# ir-tara-smd.net
KiCad netlist of a schematic drawn in Altium Designer
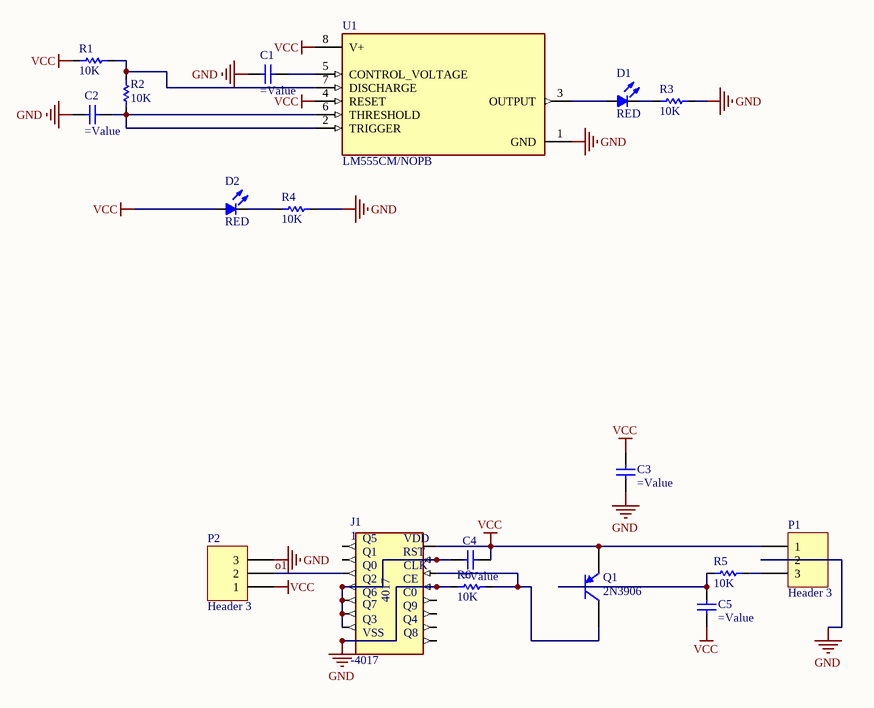
[diagram p0: ir-tara-smd.SchDoc]

(export (version "E")
  (design (tool "Eeschema 10.0.6"))
  (components
    (comp (ref "C1")
      (value "~")
      (footprint "CAP 1206")
      (description "Capacitor")
      (libsource (lib "AltiumLib1") (part "Capacitor"))
    )
    (comp (ref "C2")
      (value "~")
      (footprint "CAP 1206")
      (description "Capacitor")
      (libsource (lib "AltiumLib1") (part "Capacitor"))
    )
    (comp (ref "C3")
      (value "~")
      (footprint "CAP 1206")
      (description "Capacitor")
      (libsource (lib "AltiumLib1") (part "Capacitor"))
    )
    (comp (ref "C4")
      (value "~")
      (footprint "CAP 1206")
      (description "Capacitor")
      (libsource (lib "AltiumLib1") (part "Capacitor"))
    )
    (comp (ref "C5")
      (value "~")
      (footprint "CAP 1206")
      (description "Capacitor")
      (libsource (lib "AltiumLib1") (part "Capacitor"))
    )
    (comp (ref "D1")
      (value "MODEL")
      (footprint "LED-5mm")
      (description "Typical LED")
      (fields (field (name "COLOR") "RED"))
      (libsource (lib "AltiumLib1") (part "LED 5mm"))
    )
    (comp (ref "D2")
      (value "MODEL")
      (footprint "LED-5mm")
      (description "Typical LED")
      (fields (field (name "COLOR") "RED"))
      (libsource (lib "AltiumLib1") (part "LED 5mm"))
    )
    (comp (ref "J1")
      (value "-4017")
      (footprint "SOIC127P600X175-16N")
      (description "10000pF Â±1% 25V Ceramic Capacitor C0G, NP0 0603 (1608 Metric)")
      (fields (field (name "MF") "Heyco") (field (name "MP") "4017"))
      (libsource (lib "-4017") (part "-4017"))
    )
    (comp (ref "P1")
      (value "Header 3")
      (footprint "HDR1X3")
      (description "Header, 3-Pin")
      (fields (field (name "PUBLISHER") "Altium Limited"))
      (libsource (lib "") (part "Header 3_1"))
    )
    (comp (ref "P2")
      (value "Header 3")
      (footprint "HDR1X3")
      (description "Header, 3-Pin")
      (fields (field (name "PUBLISHER") "Altium Limited"))
      (libsource (lib "Miscellaneous Connectors") (part "Header 3"))
    )
    (comp (ref "Q1")
      (value "2N3906")
      (footprint "MMBT3904-TP:SOT23-3")
      (description "PNP General Purpose Amplifier")
      (fields (field (name "PUBLISHER") "Altium Limited"))
      (libsource (lib "Miscellaneous Devices") (part "2N3906"))
    )
    (comp (ref "R1")
      (value "10K")
      (footprint "RES 1206 (3216X08L)")
      (description "Resistor")
      (fields (field (name "TOLERANCE") "5%") (field (name "POWER") "1/4 W"))
      (libsource (lib "AltiumLib1") (part "Resistor"))
    )
    (comp (ref "R2")
      (value "10K")
      (footprint "RES 1206 (3216X08L)")
      (description "Resistor")
      (fields (field (name "TOLERANCE") "5%") (field (name "POWER") "1/4 W"))
      (libsource (lib "AltiumLib1") (part "Resistor"))
    )
    (comp (ref "R3")
      (value "10K")
      (footprint "RES 1206 (3216X08L)")
      (description "Resistor")
      (fields (field (name "TOLERANCE") "5%") (field (name "POWER") "1/4 W"))
      (libsource (lib "AltiumLib1") (part "Resistor"))
    )
    (comp (ref "R4")
      (value "10K")
      (footprint "RES 1206 (3216X08L)")
      (description "Resistor")
      (fields (field (name "TOLERANCE") "5%") (field (name "POWER") "1/4 W"))
      (libsource (lib "AltiumLib1") (part "Resistor"))
    )
    (comp (ref "R5")
      (value "10K")
      (footprint "RES 1206 (3216X08L)")
      (description "Resistor")
      (fields (field (name "TOLERANCE") "5%") (field (name "POWER") "1/4 W"))
      (libsource (lib "AltiumLib1") (part "Resistor"))
    )
    (comp (ref "R6")
      (value "10K")
      (footprint "RES 1206 (3216X08L)")
      (description "Resistor")
      (fields (field (name "TOLERANCE") "5%") (field (name "POWER") "1/4 W"))
      (libsource (lib "AltiumLib1") (part "Resistor"))
    )
    (comp (ref "U1")
      (value "LM555CM/NOPB")
      (footprint "SOIC127P599X175-8N")
      (description "Highly Stable 555 Timer 8-SOIC 0 to 70")
      (libsource (lib "LM555CM_NOPB") (part "LM555CM/NOPB"))
    )
  )
  (nets
    (net (code "1") (name "/o1") (class "Default")
      (node (ref "J1") (pin "3") (pinfunction "Q0_3") (pintype "output"))
      (node (ref "P2") (pin "2") (pinfunction "2_2") (pintype "passive"))
    )
    (net (code "2") (name "GND") (class "Default")
      (node (ref "C1") (pin "2") (pinfunction "-_2") (pintype "passive"))
      (node (ref "C2") (pin "2") (pinfunction "-_2") (pintype "passive"))
      (node (ref "C3") (pin "2") (pinfunction "-_2") (pintype "passive"))
      (node (ref "J1") (pin "13") (pinfunction "CE_13") (pintype "input"))
      (node (ref "J1") (pin "8") (pinfunction "VSS_8") (pintype "power_in"))
      (node (ref "P1") (pin "2") (pinfunction "2_2") (pintype "passive"))
      (node (ref "P2") (pin "3") (pinfunction "3_3") (pintype "passive"))
      (node (ref "R3") (pin "2") (pinfunction "2_2") (pintype "passive"))
      (node (ref "R4") (pin "2") (pinfunction "2_2") (pintype "passive"))
      (node (ref "R6") (pin "2") (pinfunction "2_2") (pintype "passive"))
      (node (ref "U1") (pin "1") (pinfunction "GND_1") (pintype "power_in"))
    )
    (net (code "3") (name "Net-(C1-+)") (class "Default")
      (node (ref "C1") (pin "1") (pinfunction "+_1") (pintype "passive"))
      (node (ref "U1") (pin "5") (pinfunction "CONTROL_VOLTAGE_5") (pintype "input"))
    )
    (net (code "4") (name "Net-(C2-+)") (class "Default")
      (node (ref "C2") (pin "1") (pinfunction "+_1") (pintype "passive"))
      (node (ref "R2") (pin "1") (pinfunction "1_1") (pintype "passive"))
      (node (ref "U1") (pin "2") (pinfunction "TRIGGER_2") (pintype "input"))
      (node (ref "U1") (pin "6") (pinfunction "THRESHOLD_6") (pintype "input"))
    )
    (net (code "5") (name "Net-(C4--)") (class "Default")
      (node (ref "C4") (pin "2") (pinfunction "-_2") (pintype "passive"))
      (node (ref "J1") (pin "15") (pinfunction "RST_15") (pintype "input"))
      (node (ref "J1") (pin "4") (pinfunction "Q2_4") (pintype "output"))
      (node (ref "J1") (pin "5") (pinfunction "Q6_5") (pintype "output"))
      (node (ref "J1") (pin "6") (pinfunction "Q7_6") (pintype "output"))
      (node (ref "J1") (pin "7") (pinfunction "Q3_7") (pintype "output"))
    )
    (net (code "6") (name "Net-(C5-+)") (class "Default")
      (node (ref "C5") (pin "1") (pinfunction "+_1") (pintype "passive"))
      (node (ref "Q1") (pin "2") (pinfunction "B_2") (pintype "passive"))
      (node (ref "R5") (pin "2") (pinfunction "2_2") (pintype "passive"))
    )
    (net (code "7") (name "Net-(D1-A)") (class "Default")
      (node (ref "D1") (pin "1") (pinfunction "A_1") (pintype "passive"))
      (node (ref "U1") (pin "3") (pinfunction "OUTPUT_3") (pintype "output"))
    )
    (net (code "8") (name "Net-(D1-K)") (class "Default")
      (node (ref "D1") (pin "2") (pinfunction "K_2") (pintype "passive"))
      (node (ref "R3") (pin "1") (pinfunction "1_1") (pintype "passive"))
    )
    (net (code "9") (name "Net-(D2-K)") (class "Default")
      (node (ref "D2") (pin "2") (pinfunction "K_2") (pintype "passive"))
      (node (ref "R4") (pin "1") (pinfunction "1_1") (pintype "passive"))
    )
    (net (code "10") (name "Net-(J1-CLK)") (class "Default")
      (node (ref "J1") (pin "14") (pinfunction "CLK_14") (pintype "input"))
      (node (ref "Q1") (pin "3") (pinfunction "C_3") (pintype "passive"))
      (node (ref "R6") (pin "1") (pinfunction "1_1") (pintype "passive"))
    )
    (net (code "11") (name "Net-(P1-Pad3)") (class "Default")
      (node (ref "P1") (pin "3") (pinfunction "3_3") (pintype "passive"))
      (node (ref "R5") (pin "1") (pinfunction "1_1") (pintype "passive"))
    )
    (net (code "12") (name "Net-(U1-DISCHARGE)") (class "Default")
      (node (ref "R1") (pin "1") (pinfunction "1_1") (pintype "passive"))
      (node (ref "R2") (pin "2") (pinfunction "2_2") (pintype "passive"))
      (node (ref "U1") (pin "7") (pinfunction "DISCHARGE_7") (pintype "input"))
    )
    (net (code "13") (name "VCC") (class "Default")
      (node (ref "C3") (pin "1") (pinfunction "+_1") (pintype "passive"))
      (node (ref "C4") (pin "1") (pinfunction "+_1") (pintype "passive"))
      (node (ref "C5") (pin "2") (pinfunction "-_2") (pintype "passive"))
      (node (ref "D2") (pin "1") (pinfunction "A_1") (pintype "passive"))
      (node (ref "J1") (pin "16") (pinfunction "VDD_16") (pintype "power_in"))
      (node (ref "P1") (pin "1") (pinfunction "1_1") (pintype "passive"))
      (node (ref "P2") (pin "1") (pinfunction "1_1") (pintype "passive"))
      (node (ref "Q1") (pin "1") (pinfunction "E_1") (pintype "passive"))
      (node (ref "R1") (pin "2") (pinfunction "2_2") (pintype "passive"))
      (node (ref "U1") (pin "4") (pinfunction "RESET_4") (pintype "input"))
      (node (ref "U1") (pin "8") (pinfunction "V+_8") (pintype "power_in"))
    )
    (net (code "14") (name "unconnected-(J1-C0-Pad12)") (class "Default")
      (node (ref "J1") (pin "12") (pinfunction "C0_12") (pintype "output"))
    )
    (net (code "15") (name "unconnected-(J1-Q1-Pad2)") (class "Default")
      (node (ref "J1") (pin "2") (pinfunction "Q1_2") (pintype "output"))
    )
    (net (code "16") (name "unconnected-(J1-Q4-Pad10)") (class "Default")
      (node (ref "J1") (pin "10") (pinfunction "Q4_10") (pintype "output"))
    )
    (net (code "17") (name "unconnected-(J1-Q5-Pad1)") (class "Default")
      (node (ref "J1") (pin "1") (pinfunction "Q5_1") (pintype "output"))
    )
    (net (code "18") (name "unconnected-(J1-Q8-Pad9)") (class "Default")
      (node (ref "J1") (pin "9") (pinfunction "Q8_9") (pintype "output"))
    )
    (net (code "19") (name "unconnected-(J1-Q9-Pad11)") (class "Default")
      (node (ref "J1") (pin "11") (pinfunction "Q9_11") (pintype "output"))
    )
  )
)
